# AdControl.net
KiCad netlist of a schematic drawn in Altium Designer
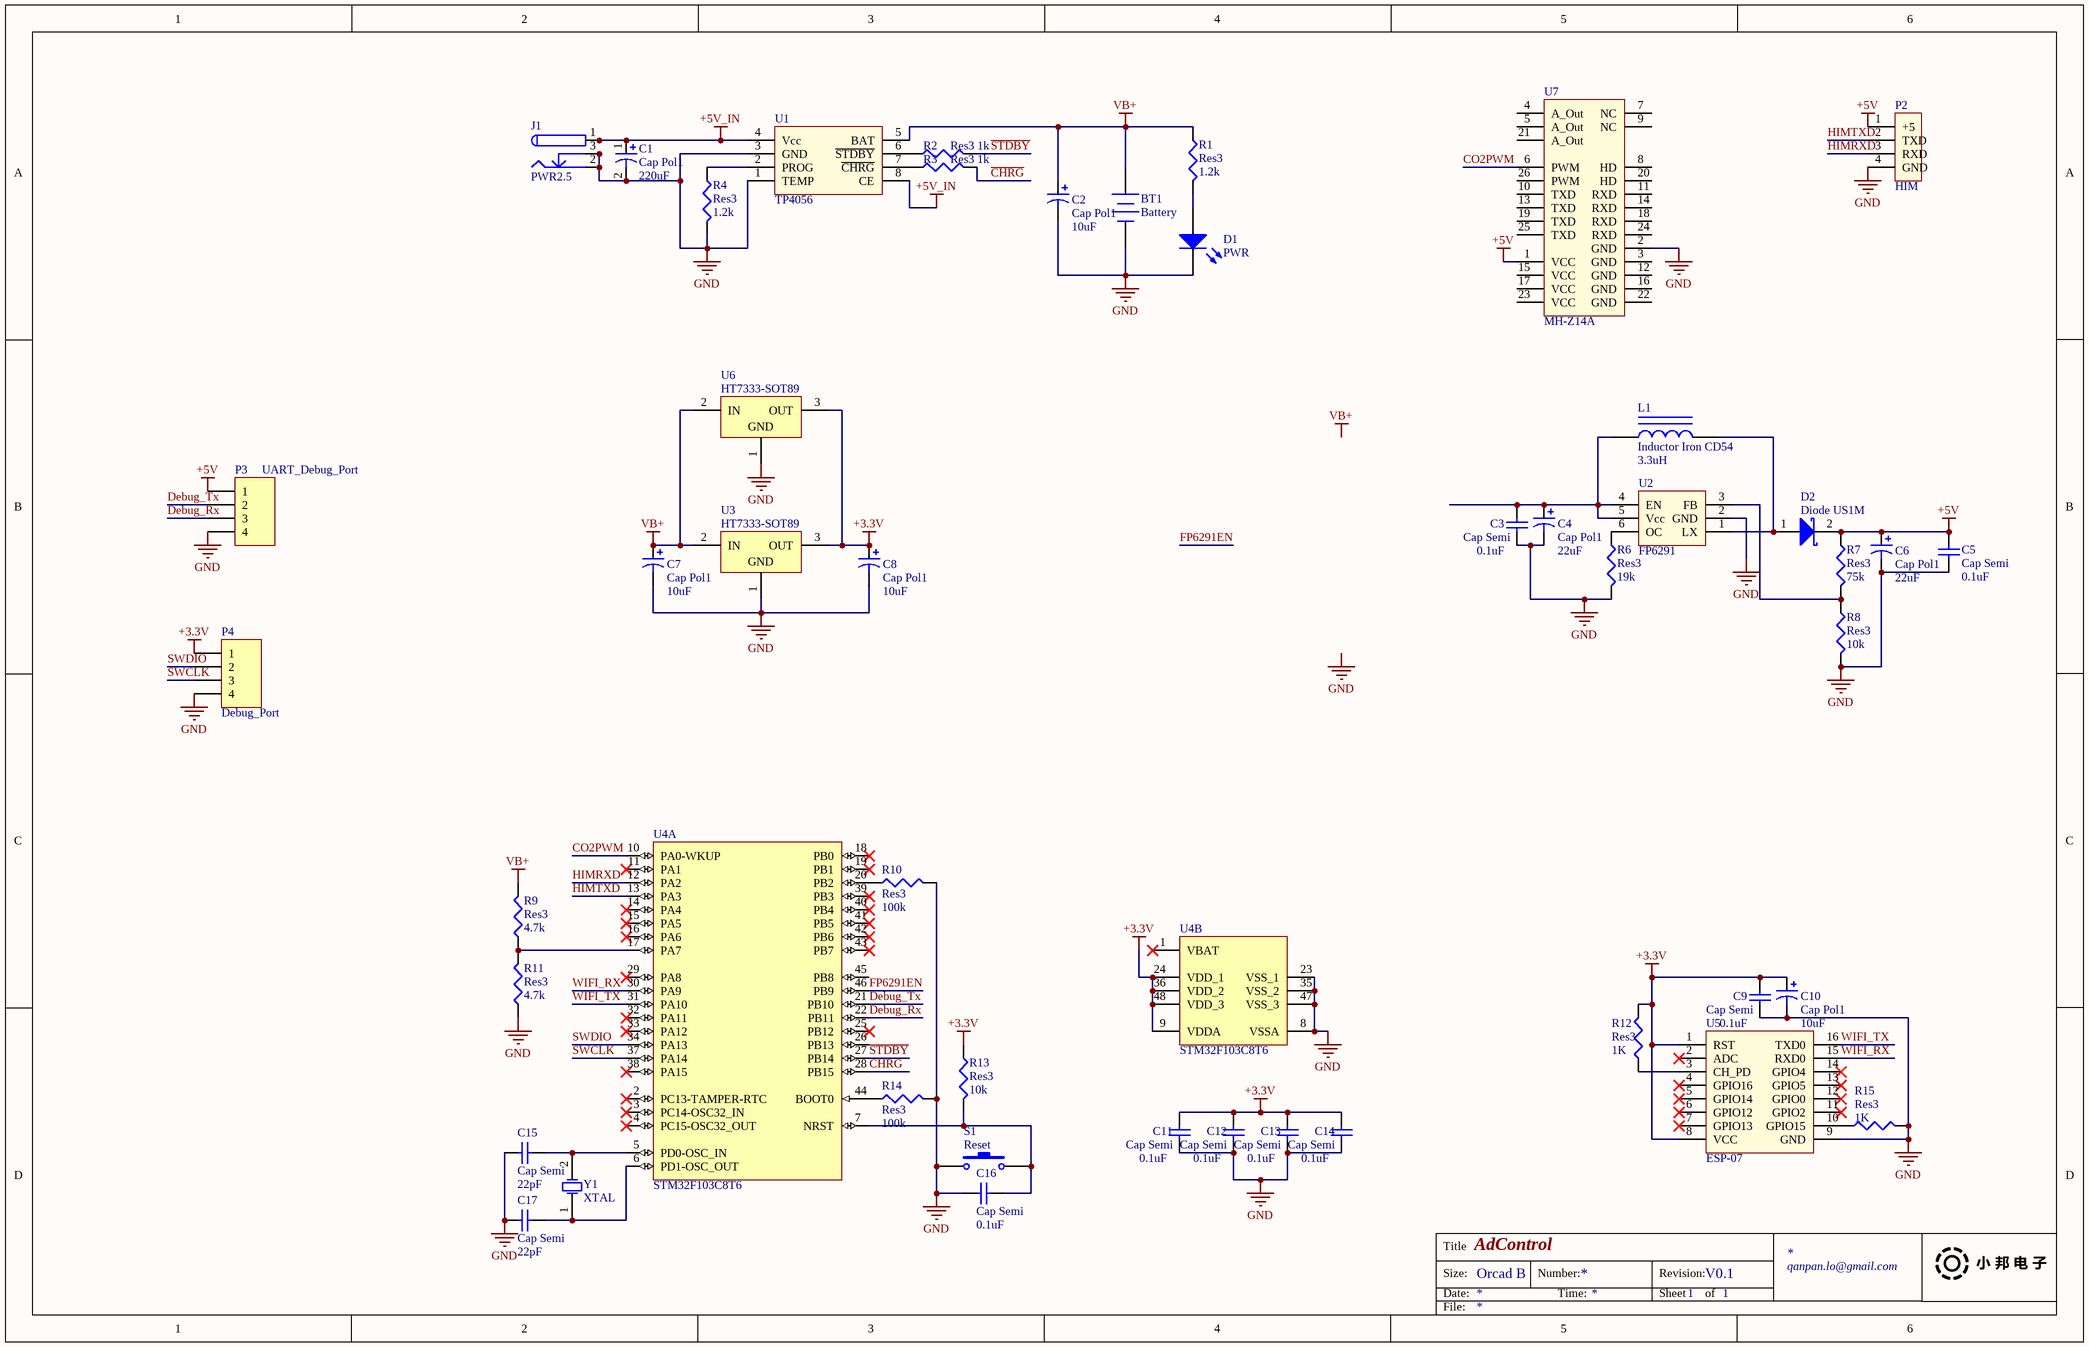
[diagram p0: AdControl.SchDoc]

(export (version "E")
  (design (tool "Eeschema 10.0.6"))
  (components
    (comp (ref "BT1")
      (value "Battery")
      (footprint "KF3.96_2P")
      (description "Multicell Battery")
      (fields (field (name "PUBLISHER") "Altium Limited"))
      (libsource (lib "Miscellaneous Devices") (part "Battery"))
    )
    (comp (ref "C1")
      (value "Cap Pol1")
      (footprint "CAP_6.3*5.4MM")
      (description "Polarized Capacitor (Radial)")
      (fields (field (name "ALTIUM_VALUE") "220uF") (field (name "PUBLISHER") "Altium Limited"))
      (libsource (lib "") (part "Cap Pol1_1"))
    )
    (comp (ref "C2")
      (value "Cap Pol1")
      (footprint "Cap_5*4mm")
      (description "Polarized Capacitor (Radial)")
      (fields (field (name "ALTIUM_VALUE") "10uF") (field (name "PUBLISHER") "Altium Limited"))
      (libsource (lib "Miscellaneous Devices") (part "Cap Pol1"))
    )
    (comp (ref "C3")
      (value "Cap Semi")
      (footprint "6-0805_N")
      (description "Capacitor (Semiconductor SIM Model)")
      (fields (field (name "ALTIUM_VALUE") "0.1uF") (field (name "PUBLISHER") "Altium Limited"))
      (libsource (lib "Miscellaneous Devices") (part "Cap Semi"))
    )
    (comp (ref "C4")
      (value "Cap Pol1")
      (footprint "Cap_5*4mm")
      (description "Polarized Capacitor (Radial)")
      (fields (field (name "ALTIUM_VALUE") "22uF") (field (name "PUBLISHER") "Altium Limited"))
      (libsource (lib "Miscellaneous Devices") (part "Cap Pol1"))
    )
    (comp (ref "C5")
      (value "Cap Semi")
      (footprint "6-0805_N")
      (description "Capacitor (Semiconductor SIM Model)")
      (fields (field (name "ALTIUM_VALUE") "0.1uF") (field (name "PUBLISHER") "Altium Limited"))
      (libsource (lib "Miscellaneous Devices") (part "Cap Semi"))
    )
    (comp (ref "C6")
      (value "Cap Pol1")
      (footprint "Cap_5*4mm")
      (description "Polarized Capacitor (Radial)")
      (fields (field (name "ALTIUM_VALUE") "22uF") (field (name "PUBLISHER") "Altium Limited"))
      (libsource (lib "Miscellaneous Devices") (part "Cap Pol1"))
    )
    (comp (ref "C7")
      (value "Cap Pol1")
      (footprint "Cap_5*4mm")
      (description "Polarized Capacitor (Radial)")
      (fields (field (name "ALTIUM_VALUE") "10uF") (field (name "PUBLISHER") "Altium Limited"))
      (libsource (lib "Miscellaneous Devices") (part "Cap Pol1"))
    )
    (comp (ref "C8")
      (value "Cap Pol1")
      (footprint "Cap_5*4mm")
      (description "Polarized Capacitor (Radial)")
      (fields (field (name "ALTIUM_VALUE") "10uF") (field (name "PUBLISHER") "Altium Limited"))
      (libsource (lib "Miscellaneous Devices") (part "Cap Pol1"))
    )
    (comp (ref "C9")
      (value "Cap Semi")
      (footprint "6-0805_N")
      (description "Capacitor (Semiconductor SIM Model)")
      (fields (field (name "ALTIUM_VALUE") "0.1uF") (field (name "PUBLISHER") "Altium Limited"))
      (libsource (lib "Miscellaneous Devices") (part "Cap Semi"))
    )
    (comp (ref "C10")
      (value "Cap Pol1")
      (footprint "Cap_5*4mm")
      (description "Polarized Capacitor (Radial)")
      (fields (field (name "ALTIUM_VALUE") "10uF") (field (name "PUBLISHER") "Altium Limited"))
      (libsource (lib "Miscellaneous Devices") (part "Cap Pol1"))
    )
    (comp (ref "C11")
      (value "Cap Semi")
      (footprint "6-0805_N")
      (description "Capacitor (Semiconductor SIM Model)")
      (fields (field (name "ALTIUM_VALUE") "0.1uF") (field (name "PUBLISHER") "Altium Limited"))
      (libsource (lib "Miscellaneous Devices") (part "Cap Semi"))
    )
    (comp (ref "C12")
      (value "Cap Semi")
      (footprint "6-0805_N")
      (description "Capacitor (Semiconductor SIM Model)")
      (fields (field (name "ALTIUM_VALUE") "0.1uF") (field (name "PUBLISHER") "Altium Limited"))
      (libsource (lib "Miscellaneous Devices") (part "Cap Semi"))
    )
    (comp (ref "C13")
      (value "Cap Semi")
      (footprint "6-0805_N")
      (description "Capacitor (Semiconductor SIM Model)")
      (fields (field (name "ALTIUM_VALUE") "0.1uF") (field (name "PUBLISHER") "Altium Limited"))
      (libsource (lib "Miscellaneous Devices") (part "Cap Semi"))
    )
    (comp (ref "C14")
      (value "Cap Semi")
      (footprint "6-0805_N")
      (description "Capacitor (Semiconductor SIM Model)")
      (fields (field (name "ALTIUM_VALUE") "0.1uF") (field (name "PUBLISHER") "Altium Limited"))
      (libsource (lib "Miscellaneous Devices") (part "Cap Semi"))
    )
    (comp (ref "C15")
      (value "Cap Semi")
      (footprint "6-0805_N")
      (description "Capacitor (Semiconductor SIM Model)")
      (fields (field (name "ALTIUM_VALUE") "22pF") (field (name "PUBLISHER") "Altium Limited"))
      (libsource (lib "Miscellaneous Devices") (part "Cap Semi"))
    )
    (comp (ref "C16")
      (value "Cap Semi")
      (footprint "6-0805_N")
      (description "Capacitor (Semiconductor SIM Model)")
      (fields (field (name "ALTIUM_VALUE") "0.1uF") (field (name "PUBLISHER") "Altium Limited"))
      (libsource (lib "Miscellaneous Devices") (part "Cap Semi"))
    )
    (comp (ref "C17")
      (value "Cap Semi")
      (footprint "6-0805_N")
      (description "Capacitor (Semiconductor SIM Model)")
      (fields (field (name "ALTIUM_VALUE") "22pF") (field (name "PUBLISHER") "Altium Limited"))
      (libsource (lib "Miscellaneous Devices") (part "Cap Semi"))
    )
    (comp (ref "D1")
      (value "PWR")
      (footprint "6-0805_N")
      (description "Typical INFRARED GaAs LED")
      (fields (field (name "PUBLISHER") "Altium Limited"))
      (libsource (lib "Miscellaneous Devices") (part "LED0"))
    )
    (comp (ref "D2")
      (value "Diode US1M")
      (footprint "US1M")
      (description "Silicon RF Schottky Diode for Mixer Applications in the VHF/UHF Range")
      (fields (field (name "PUBLISHER") "Altium Limited"))
      (libsource (lib "Miscellaneous Devices") (part "Diode BAT17"))
    )
    (comp (ref "J1")
      (value "PWR2.5")
      (footprint "KLD-3.5-1.3mm")
      (description "Low Voltage Power Supply Connector")
      (fields (field (name "PUBLISHER") "Altium Limited"))
      (libsource (lib "Miscellaneous Connectors") (part "PWR2.5"))
    )
    (comp (ref "L1")
      (value "Inductor Iron CD54")
      (footprint "CD54_Inductor")
      (description "Magnetic-Core Inductor")
      (fields (field (name "ALTIUM_VALUE") "3.3uH") (field (name "PUBLISHER") "Altium Limited"))
      (libsource (lib "Miscellaneous Devices") (part "Inductor Iron"))
    )
    (comp (ref "P2") (value "HIM") (footprint "XH2.54-4P") (libsource (lib "XH2.54") (part "XH2.54-4P")))
    (comp (ref "P3")
      (value "UART_Debug_Port")
      (footprint "HDR1X4")
      (description "Header, 4-Pin")
      (fields (field (name "PUBLISHER") "Altium Limited"))
      (libsource (lib "Miscellaneous Connectors") (part "Header 4"))
    )
    (comp (ref "P4")
      (value "Debug_Port")
      (footprint "HDR1X4")
      (description "Header, 4-Pin")
      (fields (field (name "PUBLISHER") "Altium Limited"))
      (libsource (lib "Miscellaneous Connectors") (part "Header 4"))
    )
    (comp (ref "R1")
      (value "Res3")
      (footprint "6-0805_N")
      (description "Resistor")
      (fields (field (name "ALTIUM_VALUE") "1.2k") (field (name "PUBLISHER") "Altium Limited"))
      (libsource (lib "Miscellaneous Devices") (part "Res3"))
    )
    (comp (ref "R2")
      (value "Res3")
      (footprint "6-0805_N")
      (description "Resistor")
      (fields (field (name "ALTIUM_VALUE") "1k") (field (name "PUBLISHER") "Altium Limited"))
      (libsource (lib "Miscellaneous Devices") (part "Res3"))
    )
    (comp (ref "R3")
      (value "Res3")
      (footprint "6-0805_N")
      (description "Resistor")
      (fields (field (name "ALTIUM_VALUE") "1k") (field (name "PUBLISHER") "Altium Limited"))
      (libsource (lib "Miscellaneous Devices") (part "Res3"))
    )
    (comp (ref "R4")
      (value "Res3")
      (footprint "6-0805_N")
      (description "Resistor")
      (fields (field (name "ALTIUM_VALUE") "1.2k") (field (name "PUBLISHER") "Altium Limited"))
      (libsource (lib "Miscellaneous Devices") (part "Res3"))
    )
    (comp (ref "R6")
      (value "Res3")
      (footprint "6-0805_N")
      (description "Resistor")
      (fields (field (name "ALTIUM_VALUE") "19k") (field (name "PUBLISHER") "Altium Limited"))
      (libsource (lib "Miscellaneous Devices") (part "Res3"))
    )
    (comp (ref "R7")
      (value "Res3")
      (footprint "6-0805_N")
      (description "Resistor")
      (fields (field (name "ALTIUM_VALUE") "75k") (field (name "PUBLISHER") "Altium Limited"))
      (libsource (lib "Miscellaneous Devices") (part "Res3"))
    )
    (comp (ref "R8")
      (value "Res3")
      (footprint "6-0805_N")
      (description "Resistor")
      (fields (field (name "ALTIUM_VALUE") "10k") (field (name "PUBLISHER") "Altium Limited"))
      (libsource (lib "Miscellaneous Devices") (part "Res3"))
    )
    (comp (ref "R9")
      (value "Res3")
      (footprint "6-0805_N")
      (description "Resistor")
      (fields (field (name "ALTIUM_VALUE") "4.7k") (field (name "PUBLISHER") "Altium Limited"))
      (libsource (lib "Miscellaneous Devices") (part "Res3"))
    )
    (comp (ref "R10")
      (value "Res3")
      (footprint "6-0805_N")
      (description "Resistor")
      (fields (field (name "ALTIUM_VALUE") "100k") (field (name "PUBLISHER") "Altium Limited"))
      (libsource (lib "Miscellaneous Devices") (part "Res3"))
    )
    (comp (ref "R11")
      (value "Res3")
      (footprint "6-0805_N")
      (description "Resistor")
      (fields (field (name "ALTIUM_VALUE") "4.7k") (field (name "PUBLISHER") "Altium Limited"))
      (libsource (lib "Miscellaneous Devices") (part "Res3"))
    )
    (comp (ref "R12")
      (value "Res3")
      (footprint "6-0805_N")
      (description "Resistor")
      (fields (field (name "ALTIUM_VALUE") "1K") (field (name "PUBLISHER") "Altium Limited"))
      (libsource (lib "Miscellaneous Devices") (part "Res3"))
    )
    (comp (ref "R13")
      (value "Res3")
      (footprint "6-0805_N")
      (description "Resistor")
      (fields (field (name "ALTIUM_VALUE") "10k") (field (name "PUBLISHER") "Altium Limited"))
      (libsource (lib "Miscellaneous Devices") (part "Res3"))
    )
    (comp (ref "R14")
      (value "Res3")
      (footprint "6-0805_N")
      (description "Resistor")
      (fields (field (name "ALTIUM_VALUE") "100k") (field (name "PUBLISHER") "Altium Limited"))
      (libsource (lib "Miscellaneous Devices") (part "Res3"))
    )
    (comp (ref "R15")
      (value "Res3")
      (footprint "6-0805_N")
      (description "Resistor")
      (fields (field (name "ALTIUM_VALUE") "1K") (field (name "PUBLISHER") "Altium Limited"))
      (libsource (lib "Miscellaneous Devices") (part "Res3"))
    )
    (comp (ref "S1")
      (value "Reset")
      (footprint "SWP_PB_6.5mm")
      (description "Switch")
      (fields (field (name "PUBLISHER") "Altium Limited"))
      (libsource (lib "Miscellaneous Devices") (part "SW-PB"))
    )
    (comp (ref "U1")
      (value "TP4056")
      (footprint "Power_SOP8")
      (libsource (lib "Simon'Library") (part "TP4056"))
    )
    (comp (ref "U2")
      (value "FP6291")
      (footprint "SOT23-6L")
      (libsource (lib "Simon'Library") (part "FP6291"))
    )
    (comp (ref "U3")
      (value "HT7333-SOT89")
      (footprint "SOT89_N")
      (description "Low Power Consumption LDO, Output Voltage 3.3V, SOT89 Pkg")
      (libsource (lib "Altium Content Vault") (part "PM-REG-HT73XX-IL3"))
    )
    (comp (ref "U4")
      (value "STM32F103C8T6")
      (footprint "STM-LQFP48_L")
      (libsource (lib "Altium Content Vault") (part "MC-ARM-STM32F103X8_B-SQ48"))
    )
    (comp (ref "U5")
      (value "ESP-07")
      (footprint "ESP-07_Wifi")
      (libsource (lib "Simon'Library") (part "ESP-07_Wifi"))
    )
    (comp (ref "U6")
      (value "HT7333-SOT89")
      (footprint "SOT89_N")
      (description "Low Power Consumption LDO, Output Voltage 3.3V, SOT89 Pkg")
      (libsource (lib "Altium Content Vault") (part "PM-REG-HT73XX-IL3"))
    )
    (comp (ref "U7")
      (value "MH-Z14A")
      (footprint "MH-Z14A")
      (description "CO2 Detector")
      (libsource (lib "Simon'Library") (part "MH-Z14A"))
    )
    (comp (ref "Y1")
      (value "XTAL")
      (footprint "OSC_5032_2Pin")
      (description "Crystal Oscillator")
      (fields (field (name "PUBLISHER") "Altium Limited"))
      (libsource (lib "Miscellaneous Devices") (part "XTAL"))
    )
  )
  (nets
    (net (code "1") (name "+3.3V") (class "Default")
      (node (ref "C10") (pin "1") (pinfunction "1_1") (pintype "passive"))
      (node (ref "C11") (pin "1") (pinfunction "1_1") (pintype "passive"))
      (node (ref "C12") (pin "1") (pinfunction "1_1") (pintype "passive"))
      (node (ref "C13") (pin "1") (pinfunction "1_1") (pintype "passive"))
      (node (ref "C14") (pin "1") (pinfunction "1_1") (pintype "passive"))
      (node (ref "C8") (pin "1") (pinfunction "1_1") (pintype "passive"))
      (node (ref "C9") (pin "1") (pinfunction "1_1") (pintype "passive"))
      (node (ref "P4") (pin "1") (pinfunction "1_1") (pintype "passive"))
      (node (ref "R12") (pin "2") (pinfunction "2_2") (pintype "passive"))
      (node (ref "R13") (pin "1") (pinfunction "1_1") (pintype "passive"))
      (node (ref "U3") (pin "3") (pinfunction "OUT_3") (pintype "power_in"))
      (node (ref "U4") (pin "24") (pinfunction "VDD_1_24") (pintype "power_in"))
      (node (ref "U4") (pin "36") (pinfunction "VDD_2_36") (pintype "power_in"))
      (node (ref "U4") (pin "48") (pinfunction "VDD_3_48") (pintype "power_in"))
      (node (ref "U4") (pin "9") (pinfunction "VDDA_9") (pintype "power_in"))
      (node (ref "U5") (pin "1") (pinfunction "RST_1") (pintype "passive"))
      (node (ref "U5") (pin "8") (pinfunction "VCC_8") (pintype "passive"))
      (node (ref "U6") (pin "3") (pinfunction "OUT_3") (pintype "power_in"))
    )
    (net (code "2") (name "+5V") (class "Default")
      (node (ref "C5") (pin "1") (pinfunction "1_1") (pintype "passive"))
      (node (ref "C6") (pin "1") (pinfunction "1_1") (pintype "passive"))
      (node (ref "D2") (pin "2") (pinfunction "K_2") (pintype "passive"))
      (node (ref "P2") (pin "1") (pinfunction "+5_1") (pintype "passive"))
      (node (ref "P3") (pin "1") (pinfunction "1_1") (pintype "passive"))
      (node (ref "R7") (pin "1") (pinfunction "1_1") (pintype "passive"))
      (node (ref "U7") (pin "1") (pinfunction "VCC_1") (pintype "passive"))
    )
    (net (code "3") (name "+5V_IN") (class "Default")
      (node (ref "C1") (pin "1") (pinfunction "1_1") (pintype "passive"))
      (node (ref "J1") (pin "1") (pinfunction "1_1") (pintype "power_in"))
      (node (ref "J1") (pin "1A") (pinfunction "1A_1A") (pintype "power_in"))
      (node (ref "J1") (pin "1B") (pinfunction "1B_1B") (pintype "power_in"))
      (node (ref "U1") (pin "4") (pinfunction "Vcc_4") (pintype "passive"))
      (node (ref "U1") (pin "8") (pinfunction "CE_8") (pintype "passive"))
    )
    (net (code "4") (name "/CO2PWM") (class "Default")
      (node (ref "U4") (pin "10") (pinfunction "PA0-WKUP_10") (pintype "bidirectional"))
      (node (ref "U7") (pin "6") (pinfunction "PWM_6") (pintype "passive"))
    )
    (net (code "5") (name "/Debug_Rx") (class "Default")
      (node (ref "P3") (pin "3") (pinfunction "3_3") (pintype "passive"))
      (node (ref "U4") (pin "22") (pinfunction "PB11_22") (pintype "bidirectional"))
    )
    (net (code "6") (name "/Debug_Tx") (class "Default")
      (node (ref "P3") (pin "2") (pinfunction "2_2") (pintype "passive"))
      (node (ref "U4") (pin "21") (pinfunction "PB10_21") (pintype "bidirectional"))
    )
    (net (code "7") (name "/FP6291EN") (class "Default")
      (node (ref "U4") (pin "46") (pinfunction "PB9_46") (pintype "bidirectional"))
    )
    (net (code "8") (name "/HIMRXD") (class "Default")
      (node (ref "P2") (pin "3") (pinfunction "RXD_3") (pintype "passive"))
      (node (ref "U4") (pin "12") (pinfunction "PA2_12") (pintype "bidirectional"))
    )
    (net (code "9") (name "/HIMTXD") (class "Default")
      (node (ref "P2") (pin "2") (pinfunction "TXD_2") (pintype "passive"))
      (node (ref "U4") (pin "13") (pinfunction "PA3_13") (pintype "bidirectional"))
    )
    (net (code "10") (name "/SWCLK") (class "Default")
      (node (ref "P4") (pin "3") (pinfunction "3_3") (pintype "passive"))
      (node (ref "U4") (pin "37") (pinfunction "PA14_37") (pintype "bidirectional"))
    )
    (net (code "11") (name "/SWDIO") (class "Default")
      (node (ref "P4") (pin "2") (pinfunction "2_2") (pintype "passive"))
      (node (ref "U4") (pin "34") (pinfunction "PA13_34") (pintype "bidirectional"))
    )
    (net (code "12") (name "/WIFI_RX") (class "Default")
      (node (ref "U4") (pin "30") (pinfunction "PA9_30") (pintype "bidirectional"))
      (node (ref "U5") (pin "15") (pinfunction "RXD0_15") (pintype "passive"))
    )
    (net (code "13") (name "/WIFI_TX") (class "Default")
      (node (ref "U4") (pin "31") (pinfunction "PA10_31") (pintype "bidirectional"))
      (node (ref "U5") (pin "16") (pinfunction "TXD0_16") (pintype "passive"))
    )
    (net (code "14") (name "/~{CHRG}") (class "Default")
      (node (ref "R3") (pin "2") (pinfunction "2_2") (pintype "passive"))
      (node (ref "U4") (pin "28") (pinfunction "PB15_28") (pintype "bidirectional"))
    )
    (net (code "15") (name "/~{STDBY}") (class "Default")
      (node (ref "R2") (pin "2") (pinfunction "2_2") (pintype "passive"))
      (node (ref "U4") (pin "27") (pinfunction "PB14_27") (pintype "bidirectional"))
    )
    (net (code "16") (name "GND") (class "Default")
      (node (ref "BT1") (pin "2") (pinfunction "-_2") (pintype "passive"))
      (node (ref "C1") (pin "2") (pinfunction "2_2") (pintype "passive"))
      (node (ref "C10") (pin "2") (pinfunction "2_2") (pintype "passive"))
      (node (ref "C11") (pin "2") (pinfunction "2_2") (pintype "passive"))
      (node (ref "C12") (pin "2") (pinfunction "2_2") (pintype "passive"))
      (node (ref "C13") (pin "2") (pinfunction "2_2") (pintype "passive"))
      (node (ref "C14") (pin "2") (pinfunction "2_2") (pintype "passive"))
      (node (ref "C15") (pin "2") (pinfunction "2_2") (pintype "passive"))
      (node (ref "C16") (pin "1") (pinfunction "1_1") (pintype "passive"))
      (node (ref "C17") (pin "2") (pinfunction "2_2") (pintype "passive"))
      (node (ref "C2") (pin "2") (pinfunction "2_2") (pintype "passive"))
      (node (ref "C3") (pin "2") (pinfunction "2_2") (pintype "passive"))
      (node (ref "C4") (pin "2") (pinfunction "2_2") (pintype "passive"))
      (node (ref "C5") (pin "2") (pinfunction "2_2") (pintype "passive"))
      (node (ref "C6") (pin "2") (pinfunction "2_2") (pintype "passive"))
      (node (ref "C7") (pin "2") (pinfunction "2_2") (pintype "passive"))
      (node (ref "C8") (pin "2") (pinfunction "2_2") (pintype "passive"))
      (node (ref "C9") (pin "2") (pinfunction "2_2") (pintype "passive"))
      (node (ref "D1") (pin "2") (pinfunction "K_2") (pintype "passive"))
      (node (ref "J1") (pin "2") (pinfunction "2_2") (pintype "power_in"))
      (node (ref "J1") (pin "2A") (pinfunction "2A_2A") (pintype "power_in"))
      (node (ref "J1") (pin "2B") (pinfunction "2B_2B") (pintype "power_in"))
      (node (ref "J1") (pin "3") (pinfunction "3_3") (pintype "power_in"))
      (node (ref "J1") (pin "3A") (pinfunction "3A_3A") (pintype "power_in"))
      (node (ref "J1") (pin "3B") (pinfunction "3B_3B") (pintype "power_in"))
      (node (ref "P2") (pin "4") (pinfunction "GND_4") (pintype "passive"))
      (node (ref "P3") (pin "4") (pinfunction "4_4") (pintype "passive"))
      (node (ref "P4") (pin "4") (pinfunction "4_4") (pintype "passive"))
      (node (ref "R10") (pin "2") (pinfunction "2_2") (pintype "passive"))
      (node (ref "R11") (pin "2") (pinfunction "2_2") (pintype "passive"))
      (node (ref "R14") (pin "2") (pinfunction "2_2") (pintype "passive"))
      (node (ref "R15") (pin "2") (pinfunction "2_2") (pintype "passive"))
      (node (ref "R4") (pin "2") (pinfunction "2_2") (pintype "passive"))
      (node (ref "R6") (pin "2") (pinfunction "2_2") (pintype "passive"))
      (node (ref "R8") (pin "2") (pinfunction "2_2") (pintype "passive"))
      (node (ref "S1") (pin "1") (pinfunction "1_1") (pintype "passive"))
      (node (ref "U1") (pin "1") (pinfunction "TEMP_1") (pintype "passive"))
      (node (ref "U1") (pin "3") (pinfunction "GND_3") (pintype "passive"))
      (node (ref "U2") (pin "2") (pinfunction "GND_2") (pintype "passive"))
      (node (ref "U3") (pin "1") (pinfunction "GND_1") (pintype "power_in"))
      (node (ref "U4") (pin "23") (pinfunction "VSS_1_23") (pintype "power_in"))
      (node (ref "U4") (pin "35") (pinfunction "VSS_2_35") (pintype "power_in"))
      (node (ref "U4") (pin "47") (pinfunction "VSS_3_47") (pintype "power_in"))
      (node (ref "U4") (pin "8") (pinfunction "VSSA_8") (pintype "power_in"))
      (node (ref "U5") (pin "9") (pinfunction "GND_9") (pintype "passive"))
      (node (ref "U6") (pin "1") (pinfunction "GND_1") (pintype "power_in"))
      (node (ref "U7") (pin "2") (pinfunction "GND_2") (pintype "passive"))
    )
    (net (code "17") (name "Net-(D1-A)") (class "Default")
      (node (ref "D1") (pin "1") (pinfunction "A_1") (pintype "passive"))
      (node (ref "R1") (pin "2") (pinfunction "2_2") (pintype "passive"))
    )
    (net (code "18") (name "Net-(D2-A)") (class "Default")
      (node (ref "D2") (pin "1") (pinfunction "A_1") (pintype "passive"))
      (node (ref "L1") (pin "2") (pinfunction "2_2") (pintype "passive"))
      (node (ref "U2") (pin "1") (pinfunction "LX_1") (pintype "passive"))
    )
    (net (code "19") (name "Net-(U1-PROG)") (class "Default")
      (node (ref "R4") (pin "1") (pinfunction "1_1") (pintype "passive"))
      (node (ref "U1") (pin "2") (pinfunction "PROG_2") (pintype "passive"))
    )
    (net (code "20") (name "Net-(U1-~{CHRG})") (class "Default")
      (node (ref "R3") (pin "1") (pinfunction "1_1") (pintype "passive"))
      (node (ref "U1") (pin "7") (pinfunction "~{CHRG}_7") (pintype "passive"))
    )
    (net (code "21") (name "Net-(U1-~{STDBY})") (class "Default")
      (node (ref "R2") (pin "1") (pinfunction "1_1") (pintype "passive"))
      (node (ref "U1") (pin "6") (pinfunction "~{STDBY}_6") (pintype "passive"))
    )
    (net (code "22") (name "Net-(U2-EN)") (class "Default")
      (node (ref "C3") (pin "1") (pinfunction "1_1") (pintype "passive"))
      (node (ref "C4") (pin "1") (pinfunction "1_1") (pintype "passive"))
      (node (ref "L1") (pin "1") (pinfunction "1_1") (pintype "passive"))
      (node (ref "U2") (pin "4") (pinfunction "EN_4") (pintype "passive"))
      (node (ref "U2") (pin "5") (pinfunction "Vcc_5") (pintype "passive"))
    )
    (net (code "23") (name "Net-(U2-FB)") (class "Default")
      (node (ref "R7") (pin "2") (pinfunction "2_2") (pintype "passive"))
      (node (ref "R8") (pin "1") (pinfunction "1_1") (pintype "passive"))
      (node (ref "U2") (pin "3") (pinfunction "FB_3") (pintype "passive"))
    )
    (net (code "24") (name "Net-(U2-OC)") (class "Default")
      (node (ref "R6") (pin "1") (pinfunction "1_1") (pintype "passive"))
      (node (ref "U2") (pin "6") (pinfunction "OC_6") (pintype "passive"))
    )
    (net (code "25") (name "Net-(U4A-BOOT0)") (class "Default")
      (node (ref "R14") (pin "1") (pinfunction "1_1") (pintype "passive"))
      (node (ref "U4") (pin "44") (pinfunction "BOOT0_44") (pintype "input"))
    )
    (net (code "26") (name "Net-(U4A-NRST)") (class "Default")
      (node (ref "C16") (pin "2") (pinfunction "2_2") (pintype "passive"))
      (node (ref "R13") (pin "2") (pinfunction "2_2") (pintype "passive"))
      (node (ref "S1") (pin "2") (pinfunction "2_2") (pintype "passive"))
      (node (ref "U4") (pin "7") (pinfunction "NRST_7") (pintype "bidirectional"))
    )
    (net (code "27") (name "Net-(U4A-PA7)") (class "Default")
      (node (ref "R11") (pin "1") (pinfunction "1_1") (pintype "passive"))
      (node (ref "R9") (pin "2") (pinfunction "2_2") (pintype "passive"))
      (node (ref "U4") (pin "17") (pinfunction "PA7_17") (pintype "bidirectional"))
    )
    (net (code "28") (name "Net-(U4A-PB2)") (class "Default")
      (node (ref "R10") (pin "1") (pinfunction "1_1") (pintype "passive"))
      (node (ref "U4") (pin "20") (pinfunction "PB2_20") (pintype "bidirectional"))
    )
    (net (code "29") (name "Net-(U4A-PD0-OSC_IN)") (class "Default")
      (node (ref "C15") (pin "1") (pinfunction "1_1") (pintype "passive"))
      (node (ref "U4") (pin "5") (pinfunction "PD0-OSC_IN_5") (pintype "bidirectional"))
      (node (ref "Y1") (pin "2") (pinfunction "OSC2_2") (pintype "passive"))
    )
    (net (code "30") (name "Net-(U4A-PD1-OSC_OUT)") (class "Default")
      (node (ref "C17") (pin "1") (pinfunction "1_1") (pintype "passive"))
      (node (ref "U4") (pin "6") (pinfunction "PD1-OSC_OUT_6") (pintype "bidirectional"))
      (node (ref "Y1") (pin "1") (pinfunction "OSC1_1") (pintype "passive"))
    )
    (net (code "31") (name "Net-(U5-CH_PD)") (class "Default")
      (node (ref "R12") (pin "1") (pinfunction "1_1") (pintype "passive"))
      (node (ref "U5") (pin "3") (pinfunction "CH_PD_3") (pintype "passive"))
    )
    (net (code "32") (name "Net-(U5-GPIO15)") (class "Default")
      (node (ref "R15") (pin "1") (pinfunction "1_1") (pintype "passive"))
      (node (ref "U5") (pin "10") (pinfunction "GPIO15_10") (pintype "passive"))
    )
    (net (code "33") (name "VB+") (class "Default")
      (node (ref "BT1") (pin "1") (pinfunction "+_1") (pintype "passive"))
      (node (ref "C2") (pin "1") (pinfunction "1_1") (pintype "passive"))
      (node (ref "C7") (pin "1") (pinfunction "1_1") (pintype "passive"))
      (node (ref "R1") (pin "1") (pinfunction "1_1") (pintype "passive"))
      (node (ref "R9") (pin "1") (pinfunction "1_1") (pintype "passive"))
      (node (ref "U1") (pin "5") (pinfunction "BAT_5") (pintype "passive"))
      (node (ref "U3") (pin "2") (pinfunction "IN_2") (pintype "power_in"))
      (node (ref "U6") (pin "2") (pinfunction "IN_2") (pintype "power_in"))
    )
    (net (code "34") (name "unconnected-(U4A-PA1-Pad11)") (class "Default")
      (node (ref "U4") (pin "11") (pinfunction "PA1_11") (pintype "bidirectional+no_connect"))
    )
    (net (code "35") (name "unconnected-(U4A-PA4-Pad14)") (class "Default")
      (node (ref "U4") (pin "14") (pinfunction "PA4_14") (pintype "bidirectional+no_connect"))
    )
    (net (code "36") (name "unconnected-(U4A-PA5-Pad15)") (class "Default")
      (node (ref "U4") (pin "15") (pinfunction "PA5_15") (pintype "bidirectional+no_connect"))
    )
    (net (code "37") (name "unconnected-(U4A-PA6-Pad16)") (class "Default")
      (node (ref "U4") (pin "16") (pinfunction "PA6_16") (pintype "bidirectional+no_connect"))
    )
    (net (code "38") (name "unconnected-(U4A-PA8-Pad29)") (class "Default")
      (node (ref "U4") (pin "29") (pinfunction "PA8_29") (pintype "bidirectional+no_connect"))
    )
    (net (code "39") (name "unconnected-(U4A-PA11-Pad32)") (class "Default")
      (node (ref "U4") (pin "32") (pinfunction "PA11_32") (pintype "bidirectional+no_connect"))
    )
    (net (code "40") (name "unconnected-(U4A-PA12-Pad33)") (class "Default")
      (node (ref "U4") (pin "33") (pinfunction "PA12_33") (pintype "bidirectional+no_connect"))
    )
    (net (code "41") (name "unconnected-(U4A-PA15-Pad38)") (class "Default")
      (node (ref "U4") (pin "38") (pinfunction "PA15_38") (pintype "bidirectional+no_connect"))
    )
    (net (code "42") (name "unconnected-(U4A-PB0-Pad18)") (class "Default")
      (node (ref "U4") (pin "18") (pinfunction "PB0_18") (pintype "bidirectional+no_connect"))
    )
    (net (code "43") (name "unconnected-(U4A-PB1-Pad19)") (class "Default")
      (node (ref "U4") (pin "19") (pinfunction "PB1_19") (pintype "bidirectional+no_connect"))
    )
    (net (code "44") (name "unconnected-(U4A-PB3-Pad39)") (class "Default")
      (node (ref "U4") (pin "39") (pinfunction "PB3_39") (pintype "bidirectional+no_connect"))
    )
    (net (code "45") (name "unconnected-(U4A-PB4-Pad40)") (class "Default")
      (node (ref "U4") (pin "40") (pinfunction "PB4_40") (pintype "bidirectional+no_connect"))
    )
    (net (code "46") (name "unconnected-(U4A-PB5-Pad41)") (class "Default")
      (node (ref "U4") (pin "41") (pinfunction "PB5_41") (pintype "bidirectional+no_connect"))
    )
    (net (code "47") (name "unconnected-(U4A-PB6-Pad42)") (class "Default")
      (node (ref "U4") (pin "42") (pinfunction "PB6_42") (pintype "bidirectional+no_connect"))
    )
    (net (code "48") (name "unconnected-(U4A-PB7-Pad43)") (class "Default")
      (node (ref "U4") (pin "43") (pinfunction "PB7_43") (pintype "bidirectional+no_connect"))
    )
    (net (code "49") (name "unconnected-(U4A-PB8-Pad45)") (class "Default")
      (node (ref "U4") (pin "45") (pinfunction "PB8_45") (pintype "bidirectional"))
    )
    (net (code "50") (name "unconnected-(U4A-PB12-Pad25)") (class "Default")
      (node (ref "U4") (pin "25") (pinfunction "PB12_25") (pintype "bidirectional+no_connect"))
    )
    (net (code "51") (name "unconnected-(U4A-PB13-Pad26)") (class "Default")
      (node (ref "U4") (pin "26") (pinfunction "PB13_26") (pintype "bidirectional"))
    )
    (net (code "52") (name "unconnected-(U4A-PC13-TAMPER-RTC-Pad2)") (class "Default")
      (node (ref "U4") (pin "2") (pinfunction "PC13-TAMPER-RTC_2") (pintype "bidirectional+no_connect"))
    )
    (net (code "53") (name "unconnected-(U4A-PC14-OSC32_IN-Pad3)") (class "Default")
      (node (ref "U4") (pin "3") (pinfunction "PC14-OSC32_IN_3") (pintype "bidirectional+no_connect"))
    )
    (net (code "54") (name "unconnected-(U4A-PC15-OSC32_OUT-Pad4)") (class "Default")
      (node (ref "U4") (pin "4") (pinfunction "PC15-OSC32_OUT_4") (pintype "bidirectional+no_connect"))
    )
    (net (code "55") (name "unconnected-(U4B-VBAT-Pad1)") (class "Default")
      (node (ref "U4") (pin "1") (pinfunction "VBAT_1") (pintype "power_in+no_connect"))
    )
    (net (code "56") (name "unconnected-(U5-ADC-Pad2)") (class "Default")
      (node (ref "U5") (pin "2") (pinfunction "ADC_2") (pintype "passive+no_connect"))
    )
    (net (code "57") (name "unconnected-(U5-GPIO0-Pad12)") (class "Default")
      (node (ref "U5") (pin "12") (pinfunction "GPIO0_12") (pintype "passive+no_connect"))
    )
    (net (code "58") (name "unconnected-(U5-GPIO2-Pad11)") (class "Default")
      (node (ref "U5") (pin "11") (pinfunction "GPIO2_11") (pintype "passive+no_connect"))
    )
    (net (code "59") (name "unconnected-(U5-GPIO4-Pad14)") (class "Default")
      (node (ref "U5") (pin "14") (pinfunction "GPIO4_14") (pintype "passive+no_connect"))
    )
    (net (code "60") (name "unconnected-(U5-GPIO5-Pad13)") (class "Default")
      (node (ref "U5") (pin "13") (pinfunction "GPIO5_13") (pintype "passive+no_connect"))
    )
    (net (code "61") (name "unconnected-(U5-GPIO12-Pad6)") (class "Default")
      (node (ref "U5") (pin "6") (pinfunction "GPIO12_6") (pintype "passive+no_connect"))
    )
    (net (code "62") (name "unconnected-(U5-GPIO13-Pad7)") (class "Default")
      (node (ref "U5") (pin "7") (pinfunction "GPIO13_7") (pintype "passive+no_connect"))
    )
    (net (code "63") (name "unconnected-(U5-GPIO14-Pad5)") (class "Default")
      (node (ref "U5") (pin "5") (pinfunction "GPIO14_5") (pintype "passive+no_connect"))
    )
    (net (code "64") (name "unconnected-(U5-GPIO16-Pad4)") (class "Default")
      (node (ref "U5") (pin "4") (pinfunction "GPIO16_4") (pintype "passive+no_connect"))
    )
    (net (code "65") (name "unconnected-(U7-A_Out-Pad4)") (class "Default")
      (node (ref "U7") (pin "4") (pinfunction "A_Out_4") (pintype "passive"))
    )
    (net (code "66") (name "unconnected-(U7-A_Out-Pad5)") (class "Default")
      (node (ref "U7") (pin "5") (pinfunction "A_Out_5") (pintype "passive"))
    )
    (net (code "67") (name "unconnected-(U7-A_Out-Pad21)") (class "Default")
      (node (ref "U7") (pin "21") (pinfunction "A_Out_21") (pintype "passive"))
    )
    (net (code "68") (name "unconnected-(U7-GND-Pad3)") (class "Default")
      (node (ref "U7") (pin "3") (pinfunction "GND_3") (pintype "passive"))
    )
    (net (code "69") (name "unconnected-(U7-GND-Pad12)") (class "Default")
      (node (ref "U7") (pin "12") (pinfunction "GND_12") (pintype "passive"))
    )
    (net (code "70") (name "unconnected-(U7-GND-Pad16)") (class "Default")
      (node (ref "U7") (pin "16") (pinfunction "GND_16") (pintype "passive"))
    )
    (net (code "71") (name "unconnected-(U7-GND-Pad22)") (class "Default")
      (node (ref "U7") (pin "22") (pinfunction "GND_22") (pintype "passive"))
    )
    (net (code "72") (name "unconnected-(U7-HD-Pad8)") (class "Default")
      (node (ref "U7") (pin "8") (pinfunction "HD_8") (pintype "passive"))
    )
    (net (code "73") (name "unconnected-(U7-HD-Pad20)") (class "Default")
      (node (ref "U7") (pin "20") (pinfunction "HD_20") (pintype "passive"))
    )
    (net (code "74") (name "unconnected-(U7-NC-Pad7)") (class "Default")
      (node (ref "U7") (pin "7") (pinfunction "NC_7") (pintype "passive"))
    )
    (net (code "75") (name "unconnected-(U7-NC-Pad9)") (class "Default")
      (node (ref "U7") (pin "9") (pinfunction "NC_9") (pintype "passive"))
    )
    (net (code "76") (name "unconnected-(U7-PWM-Pad26)") (class "Default")
      (node (ref "U7") (pin "26") (pinfunction "PWM_26") (pintype "passive"))
    )
    (net (code "77") (name "unconnected-(U7-RXD-Pad11)") (class "Default")
      (node (ref "U7") (pin "11") (pinfunction "RXD_11") (pintype "passive"))
    )
    (net (code "78") (name "unconnected-(U7-RXD-Pad14)") (class "Default")
      (node (ref "U7") (pin "14") (pinfunction "RXD_14") (pintype "passive"))
    )
    (net (code "79") (name "unconnected-(U7-RXD-Pad18)") (class "Default")
      (node (ref "U7") (pin "18") (pinfunction "RXD_18") (pintype "passive"))
    )
    (net (code "80") (name "unconnected-(U7-RXD-Pad24)") (class "Default")
      (node (ref "U7") (pin "24") (pinfunction "RXD_24") (pintype "passive"))
    )
    (net (code "81") (name "unconnected-(U7-TXD-Pad10)") (class "Default")
      (node (ref "U7") (pin "10") (pinfunction "TXD_10") (pintype "passive"))
    )
    (net (code "82") (name "unconnected-(U7-TXD-Pad13)") (class "Default")
      (node (ref "U7") (pin "13") (pinfunction "TXD_13") (pintype "passive"))
    )
    (net (code "83") (name "unconnected-(U7-TXD-Pad19)") (class "Default")
      (node (ref "U7") (pin "19") (pinfunction "TXD_19") (pintype "passive"))
    )
    (net (code "84") (name "unconnected-(U7-TXD-Pad25)") (class "Default")
      (node (ref "U7") (pin "25") (pinfunction "TXD_25") (pintype "passive"))
    )
    (net (code "85") (name "unconnected-(U7-VCC-Pad15)") (class "Default")
      (node (ref "U7") (pin "15") (pinfunction "VCC_15") (pintype "passive"))
    )
    (net (code "86") (name "unconnected-(U7-VCC-Pad17)") (class "Default")
      (node (ref "U7") (pin "17") (pinfunction "VCC_17") (pintype "passive"))
    )
    (net (code "87") (name "unconnected-(U7-VCC-Pad23)") (class "Default")
      (node (ref "U7") (pin "23") (pinfunction "VCC_23") (pintype "passive"))
    )
  )
)
